# Schematic_rtpMIDI.net
KiCad netlist of a schematic drawn in EAGLE
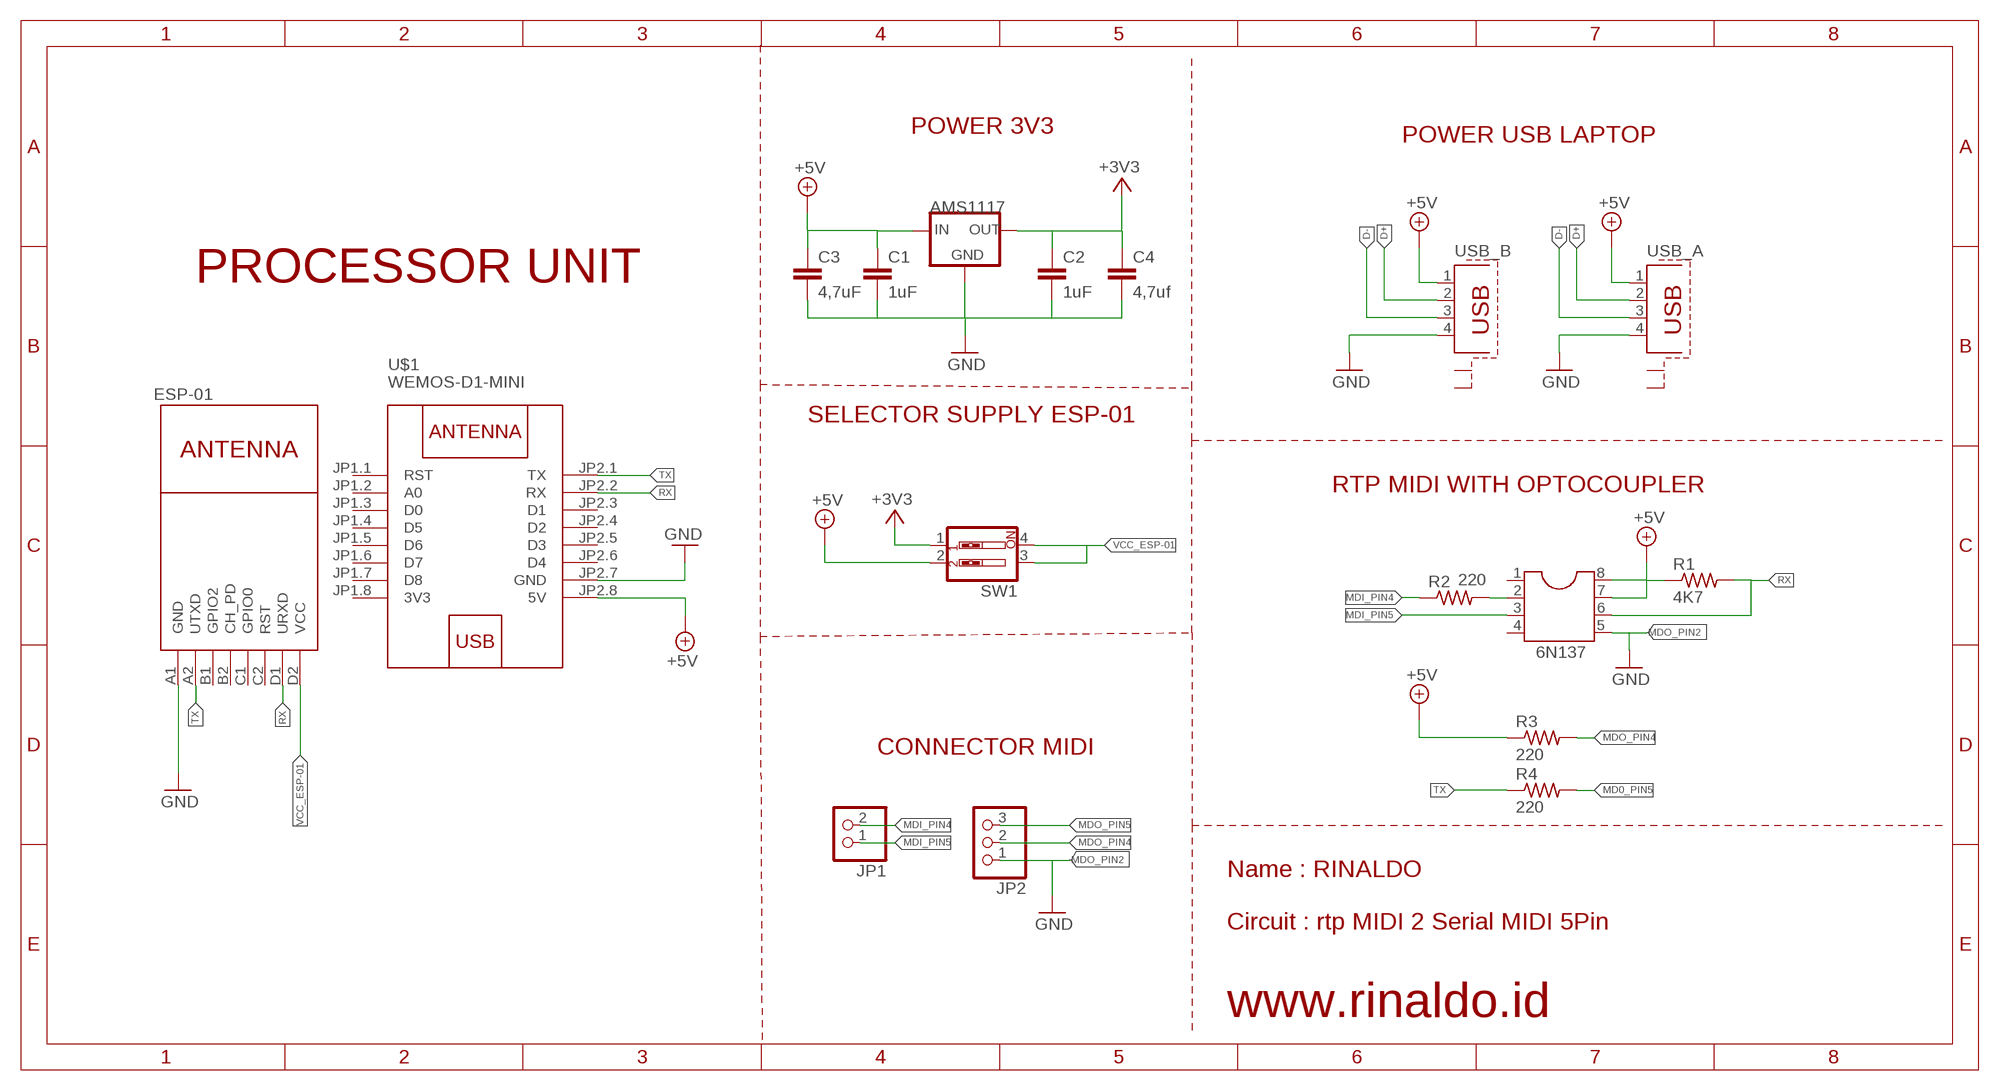
[diagram p0: schematic, sheet 1]

(export (version "E")
  (design (tool "Eeschema 10.0.6"))
  (components
    (comp (ref "6N137")
      (value "DIL8S")
      (footprint "eagle-import:SOCKET-08")
      (libsource (lib "eagle-import") (part "DIL8S"))
    )
    (comp (ref "AMS1117")
      (value "V_REG_LD1117VXXLD1117-SMD")
      (footprint "eagle-import:SOT223")
      (libsource (lib "eagle-import") (part "V_REG_LD1117VXXLD1117-SMD"))
    )
    (comp (ref "C1")
      (value "1uF")
      (footprint "eagle-import:C0805")
      (libsource (lib "eagle-import") (part "C-EUC0805"))
    )
    (comp (ref "C2")
      (value "1uF")
      (footprint "eagle-import:C0805")
      (libsource (lib "eagle-import") (part "C-EUC0805"))
    )
    (comp (ref "C3")
      (value "4,7uF")
      (footprint "eagle-import:C0805")
      (libsource (lib "eagle-import") (part "C-EUC0805"))
    )
    (comp (ref "C4")
      (value "4,7uf")
      (footprint "eagle-import:C0805")
      (libsource (lib "eagle-import") (part "C-EUC0805"))
    )
    (comp (ref "ESP-01")
      (value "WIRELESS-WIFI-ESP-01")
      (footprint "eagle-import:WIRELESS-WIFI-ESP-01")
      (libsource (lib "eagle-import") (part "WIRELESS-WIFI-ESP-01"))
    )
    (comp (ref "JP1")
      (value "PINHD-1X2")
      (footprint "eagle-import:1X02")
      (libsource (lib "eagle-import") (part "PINHD-1X2"))
    )
    (comp (ref "JP2")
      (value "PINHD-1X3")
      (footprint "eagle-import:1X03")
      (libsource (lib "eagle-import") (part "PINHD-1X3"))
    )
    (comp (ref "R1")
      (value "4K7")
      (footprint "eagle-import:M0805")
      (libsource (lib "eagle-import") (part "R-US_M0805"))
    )
    (comp (ref "R2")
      (value "220")
      (footprint "eagle-import:M0805")
      (libsource (lib "eagle-import") (part "R-US_M0805"))
    )
    (comp (ref "R3")
      (value "220")
      (footprint "eagle-import:M0805")
      (libsource (lib "eagle-import") (part "R-US_M0805"))
    )
    (comp (ref "R4")
      (value "220")
      (footprint "eagle-import:M0805")
      (libsource (lib "eagle-import") (part "R-US_M0805"))
    )
    (comp (ref "SW1")
      (value "SW_DIP-2")
      (footprint "eagle-import:EDG-02")
      (libsource (lib "eagle-import") (part "SW_DIP-2"))
    )
    (comp (ref "U$1")
      (value "WEMOS-D1-MINI")
      (footprint "eagle-import:WEMOS-D1-MINI")
      (libsource (lib "eagle-import") (part "WEMOS-D1-MINI"))
    )
    (comp (ref "USB_A")
      (value "PN87520-S")
      (footprint "eagle-import:PN87520-S")
      (libsource (lib "eagle-import") (part "PN87520-S"))
    )
    (comp (ref "USB_B")
      (value "PN61729-S")
      (footprint "eagle-import:PN61729-S")
      (libsource (lib "eagle-import") (part "PN61729-S"))
    )
  )
  (nets
    (net (code "1") (name "+3V3") (class "Default")
      (node (ref "AMS1117") (pin "2") (pinfunction "OUT_2") (pintype "passive"))
      (node (ref "C2") (pin "1") (pinfunction "1_1") (pintype "passive"))
      (node (ref "C4") (pin "1") (pinfunction "1_1") (pintype "passive"))
      (node (ref "SW1") (pin "1") (pinfunction "1_1") (pintype "passive"))
    )
    (net (code "2") (name "+5V") (class "Default")
      (node (ref "6N137") (pin "7") (pinfunction "7_7") (pintype "passive"))
      (node (ref "6N137") (pin "8") (pinfunction "8_8") (pintype "passive"))
      (node (ref "AMS1117") (pin "3") (pinfunction "IN_3") (pintype "input"))
      (node (ref "C1") (pin "1") (pinfunction "1_1") (pintype "passive"))
      (node (ref "C3") (pin "1") (pinfunction "1_1") (pintype "passive"))
      (node (ref "R1") (pin "1") (pinfunction "1_1") (pintype "passive"))
      (node (ref "R3") (pin "1") (pinfunction "1_1") (pintype "passive"))
      (node (ref "SW1") (pin "2") (pinfunction "2_2") (pintype "passive"))
      (node (ref "U$1") (pin "JP2.8") (pinfunction "5V_JP2.8") (pintype "power_in"))
      (node (ref "USB_A") (pin "1") (pinfunction "1_1") (pintype "passive"))
      (node (ref "USB_B") (pin "1") (pinfunction "1_1") (pintype "passive"))
    )
    (net (code "3") (name "/3V3") (class "Default")
      (node (ref "U$1") (pin "JP1.8") (pinfunction "3V3_JP1.8") (pintype "power_in"))
    )
    (net (code "4") (name "D+") (class "Default")
      (node (ref "USB_A") (pin "2") (pinfunction "2_2") (pintype "passive"))
      (node (ref "USB_B") (pin "2") (pinfunction "2_2") (pintype "passive"))
    )
    (net (code "5") (name "D-") (class "Default")
      (node (ref "USB_A") (pin "3") (pinfunction "3_3") (pintype "passive"))
      (node (ref "USB_B") (pin "3") (pinfunction "3_3") (pintype "passive"))
    )
    (net (code "6") (name "GND") (class "Default")
      (node (ref "6N137") (pin "5") (pinfunction "5_5") (pintype "passive"))
      (node (ref "AMS1117") (pin "1") (pinfunction "GND_1") (pintype "input"))
      (node (ref "C1") (pin "2") (pinfunction "2_2") (pintype "passive"))
      (node (ref "C2") (pin "2") (pinfunction "2_2") (pintype "passive"))
      (node (ref "C3") (pin "2") (pinfunction "2_2") (pintype "passive"))
      (node (ref "C4") (pin "2") (pinfunction "2_2") (pintype "passive"))
      (node (ref "ESP-01") (pin "A1") (pinfunction "GND_A1") (pintype "power_in"))
      (node (ref "JP2") (pin "1") (pinfunction "1_1") (pintype "passive"))
      (node (ref "U$1") (pin "JP2.7") (pinfunction "GND_JP2.7") (pintype "power_in"))
      (node (ref "USB_A") (pin "4") (pinfunction "4_4") (pintype "passive"))
      (node (ref "USB_B") (pin "4") (pinfunction "4_4") (pintype "passive"))
    )
    (net (code "7") (name "MD0_PIN5") (class "Default")
      (node (ref "R4") (pin "2") (pinfunction "2_2") (pintype "passive"))
    )
    (net (code "8") (name "MDI_PIN4") (class "Default")
      (node (ref "JP1") (pin "2") (pinfunction "2_2") (pintype "passive"))
      (node (ref "R2") (pin "1") (pinfunction "1_1") (pintype "passive"))
    )
    (net (code "9") (name "MDI_PIN5") (class "Default")
      (node (ref "6N137") (pin "3") (pinfunction "3_3") (pintype "passive"))
      (node (ref "JP1") (pin "1") (pinfunction "1_1") (pintype "passive"))
    )
    (net (code "10") (name "MDO_PIN4") (class "Default")
      (node (ref "JP2") (pin "2") (pinfunction "2_2") (pintype "passive"))
      (node (ref "R3") (pin "2") (pinfunction "2_2") (pintype "passive"))
    )
    (net (code "11") (name "MDO_PIN5") (class "Default")
      (node (ref "JP2") (pin "3") (pinfunction "3_3") (pintype "passive"))
    )
    (net (code "12") (name "Net-(6N137-Pad2)") (class "Default")
      (node (ref "6N137") (pin "2") (pinfunction "2_2") (pintype "passive"))
      (node (ref "R2") (pin "2") (pinfunction "2_2") (pintype "passive"))
    )
    (net (code "13") (name "RX") (class "Default")
      (node (ref "6N137") (pin "6") (pinfunction "6_6") (pintype "passive"))
      (node (ref "ESP-01") (pin "D1") (pinfunction "URXD_D1") (pintype "bidirectional"))
      (node (ref "R1") (pin "2") (pinfunction "2_2") (pintype "passive"))
      (node (ref "U$1") (pin "JP2.2") (pinfunction "RX_JP2.2") (pintype "bidirectional"))
    )
    (net (code "14") (name "TX") (class "Default")
      (node (ref "ESP-01") (pin "A2") (pinfunction "UTXD_A2") (pintype "bidirectional"))
      (node (ref "R4") (pin "1") (pinfunction "1_1") (pintype "passive"))
      (node (ref "U$1") (pin "JP2.1") (pinfunction "TX_JP2.1") (pintype "bidirectional"))
    )
    (net (code "15") (name "VCC_ESP-01") (class "Default")
      (node (ref "ESP-01") (pin "D2") (pinfunction "VCC_D2") (pintype "power_in"))
      (node (ref "SW1") (pin "3") (pinfunction "3_3") (pintype "passive"))
      (node (ref "SW1") (pin "4") (pinfunction "4_4") (pintype "passive"))
    )
    (net (code "16") (name "unconnected-(6N137-Pad1)") (class "Default")
      (node (ref "6N137") (pin "1") (pinfunction "1_1") (pintype "passive"))
    )
    (net (code "17") (name "unconnected-(6N137-Pad4)") (class "Default")
      (node (ref "6N137") (pin "4") (pinfunction "4_4") (pintype "passive"))
    )
    (net (code "18") (name "unconnected-(ESP-01-CH_PD-PadB2)") (class "Default")
      (node (ref "ESP-01") (pin "B2") (pinfunction "CH_PD_B2") (pintype "bidirectional"))
    )
    (net (code "19") (name "unconnected-(ESP-01-GPIO0-PadC1)") (class "Default")
      (node (ref "ESP-01") (pin "C1") (pinfunction "GPIO0_C1") (pintype "bidirectional"))
    )
    (net (code "20") (name "unconnected-(ESP-01-GPIO2-PadB1)") (class "Default")
      (node (ref "ESP-01") (pin "B1") (pinfunction "GPIO2_B1") (pintype "bidirectional"))
    )
    (net (code "21") (name "unconnected-(ESP-01-RST-PadC2)") (class "Default")
      (node (ref "ESP-01") (pin "C2") (pinfunction "RST_C2") (pintype "bidirectional"))
    )
    (net (code "22") (name "unconnected-(U$1-A0-PadJP1.2)") (class "Default")
      (node (ref "U$1") (pin "JP1.2") (pinfunction "A0_JP1.2") (pintype "bidirectional"))
    )
    (net (code "23") (name "unconnected-(U$1-D0-PadJP1.3)") (class "Default")
      (node (ref "U$1") (pin "JP1.3") (pinfunction "D0_JP1.3") (pintype "bidirectional"))
    )
    (net (code "24") (name "unconnected-(U$1-D1-PadJP2.3)") (class "Default")
      (node (ref "U$1") (pin "JP2.3") (pinfunction "D1_JP2.3") (pintype "bidirectional"))
    )
    (net (code "25") (name "unconnected-(U$1-D2-PadJP2.4)") (class "Default")
      (node (ref "U$1") (pin "JP2.4") (pinfunction "D2_JP2.4") (pintype "bidirectional"))
    )
    (net (code "26") (name "unconnected-(U$1-D3-PadJP2.5)") (class "Default")
      (node (ref "U$1") (pin "JP2.5") (pinfunction "D3_JP2.5") (pintype "bidirectional"))
    )
    (net (code "27") (name "unconnected-(U$1-D4-PadJP2.6)") (class "Default")
      (node (ref "U$1") (pin "JP2.6") (pinfunction "D4_JP2.6") (pintype "bidirectional"))
    )
    (net (code "28") (name "unconnected-(U$1-D5-PadJP1.4)") (class "Default")
      (node (ref "U$1") (pin "JP1.4") (pinfunction "D5_JP1.4") (pintype "bidirectional"))
    )
    (net (code "29") (name "unconnected-(U$1-D6-PadJP1.5)") (class "Default")
      (node (ref "U$1") (pin "JP1.5") (pinfunction "D6_JP1.5") (pintype "bidirectional"))
    )
    (net (code "30") (name "unconnected-(U$1-D7-PadJP1.6)") (class "Default")
      (node (ref "U$1") (pin "JP1.6") (pinfunction "D7_JP1.6") (pintype "bidirectional"))
    )
    (net (code "31") (name "unconnected-(U$1-D8-PadJP1.7)") (class "Default")
      (node (ref "U$1") (pin "JP1.7") (pinfunction "D8_JP1.7") (pintype "bidirectional"))
    )
    (net (code "32") (name "unconnected-(U$1-RST-PadJP1.1)") (class "Default")
      (node (ref "U$1") (pin "JP1.1") (pinfunction "RST_JP1.1") (pintype "bidirectional"))
    )
    (net (code "33") (name "unconnected-(USB_A-PadS1)") (class "Default")
      (node (ref "USB_A") (pin "S1") (pinfunction "S1_S1") (pintype "passive"))
    )
    (net (code "34") (name "unconnected-(USB_A-PadS2)") (class "Default")
      (node (ref "USB_A") (pin "S2") (pinfunction "S2_S2") (pintype "passive"))
    )
    (net (code "35") (name "unconnected-(USB_B-PadS1)") (class "Default")
      (node (ref "USB_B") (pin "S1") (pinfunction "S1_S1") (pintype "passive"))
    )
    (net (code "36") (name "unconnected-(USB_B-PadS2)") (class "Default")
      (node (ref "USB_B") (pin "S2") (pinfunction "S2_S2") (pintype "passive"))
    )
  )
)
